# THS7002CPWP_Schematic_2.net
KiCad netlist of a schematic drawn in Altium Designer
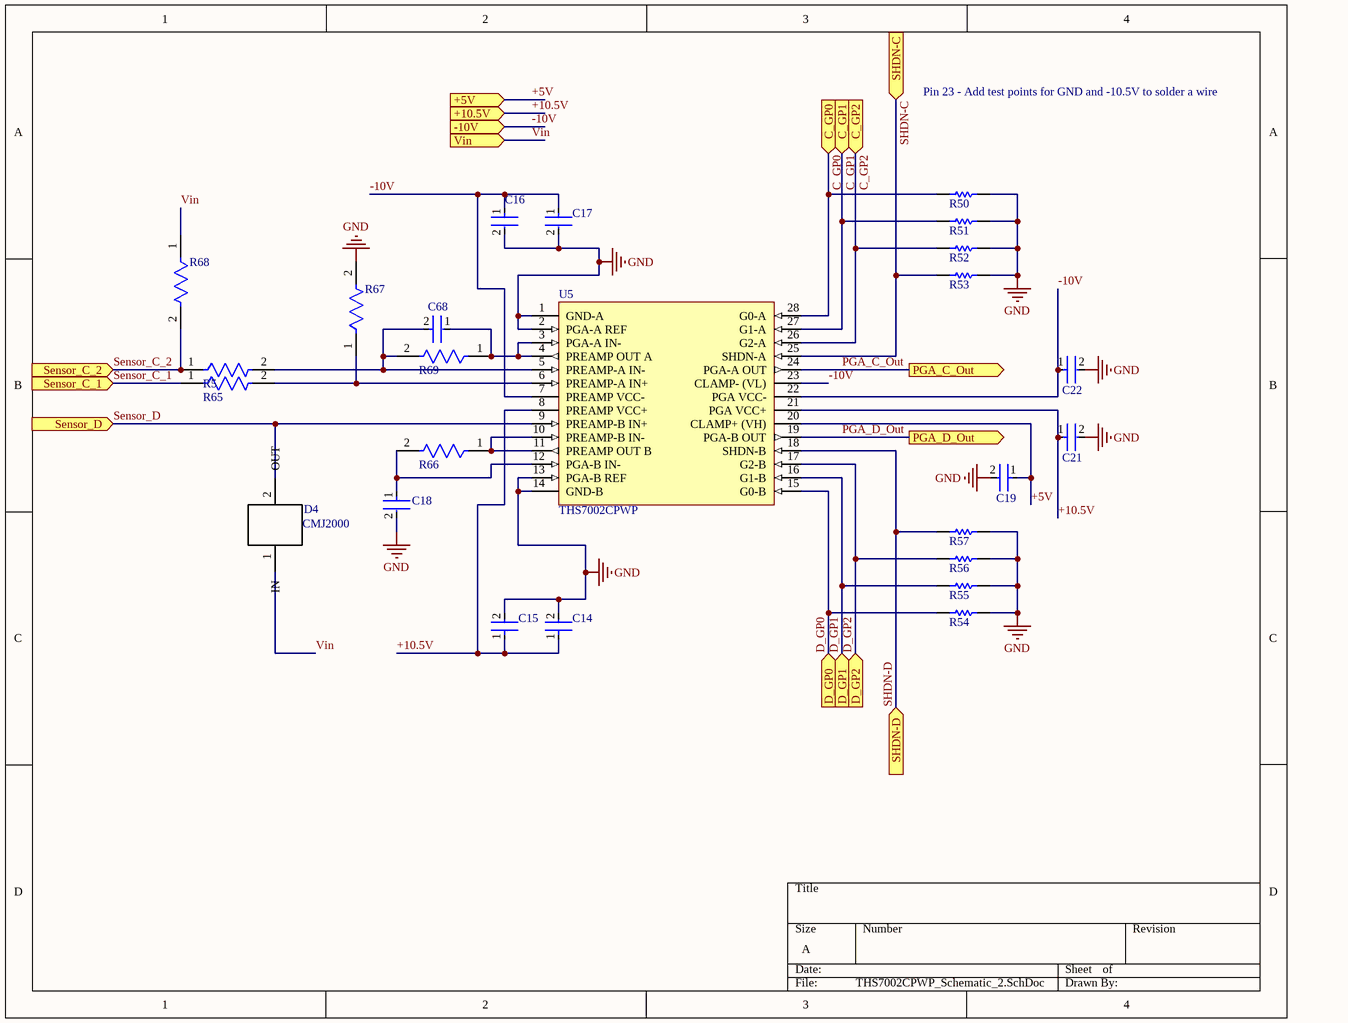
[diagram p0: THS7002CPWP_Schematic_2.SchDoc]

(export (version "E")
  (design (tool "Eeschema 10.0.6"))
  (components
    (comp (ref "C14")
      (value "~")
      (footprint "FP-C2012-060-0_2-IPC_A")
      (description "Multilayer Ceramic Capacitors 6.8μF ±10% 10V JB SMD 0805")
      (fields (field (name "TOLERANCE") "10%"))
      (libsource (lib "Capacitors") (part "b4654b650e69147ec39a6b967a45e02"))
    )
    (comp (ref "C15")
      (value "CC0603KRX7R7BB104")
      (footprint "FP-CC0603-DA-MFG")
      (description "CAP CER 0.1UF 16V X7R 0603")
      (fields
        (field (name "OCTOPART") "https://octopart.com/cc0603krx7r7bb104-yageo-192941")
        (field (name "TOLERANCE") "0.1")
      )
      (libsource (lib "Altium Content Vault") (part "11868f565c42a9108669ba33697ecf6"))
    )
    (comp (ref "C16")
      (value "CC0603KRX7R7BB104")
      (footprint "FP-CC0603-DA-MFG")
      (description "CAP CER 0.1UF 16V X7R 0603")
      (fields
        (field (name "OCTOPART") "https://octopart.com/cc0603krx7r7bb104-yageo-192941")
        (field (name "TOLERANCE") "0.1")
      )
      (libsource (lib "Altium Content Vault") (part "11868f565c42a9108669ba33697ecf6"))
    )
    (comp (ref "C17")
      (value "~")
      (footprint "FP-C2012-060-0_2-IPC_A")
      (description "Multilayer Ceramic Capacitors 6.8μF ±10% 10V JB SMD 0805")
      (fields (field (name "TOLERANCE") "10%"))
      (libsource (lib "Capacitors") (part "b4654b650e69147ec39a6b967a45e02"))
    )
    (comp (ref "C18")
      (value "GRM2195C1H622JA01D")
      (footprint "FP-GRM219-0_1-IPC_C")
      (description "Chip Multilayer Ceramic Capacitors for General Purpose, 0805, 6200pF, C0G, 30ppm/°C, 5%, 50V")
      (fields (field (name "TOLERANCE") "5%") (field (name "VOLTAGE") "50V"))
      (libsource (lib "Altium Content Vault") (part "02cd4be3c70576c341d710602a673aa"))
    )
    (comp (ref "C19")
      (value "~")
      (footprint "FP-C2012-060-0_2-IPC_A")
      (description "Multilayer Ceramic Capacitors 6.8μF ±10% 10V JB SMD 0805")
      (fields (field (name "TOLERANCE") "10%"))
      (libsource (lib "Capacitors") (part "b4654b650e69147ec39a6b967a45e02"))
    )
    (comp (ref "C21")
      (value "CC0603KRX7R7BB104")
      (footprint "FP-CC0603-DA-MFG")
      (description "CAP CER 0.1UF 16V X7R 0603")
      (fields
        (field (name "OCTOPART") "https://octopart.com/cc0603krx7r7bb104-yageo-192941")
        (field (name "TOLERANCE") "0.1")
      )
      (libsource (lib "Altium Content Vault") (part "11868f565c42a9108669ba33697ecf6"))
    )
    (comp (ref "C22")
      (value "CC0603KRX7R7BB104")
      (footprint "FP-CC0603-DA-MFG")
      (description "CAP CER 0.1UF 16V X7R 0603")
      (fields
        (field (name "OCTOPART") "https://octopart.com/cc0603krx7r7bb104-yageo-192941")
        (field (name "TOLERANCE") "0.1")
      )
      (libsource (lib "Altium Content Vault") (part "11868f565c42a9108669ba33697ecf6"))
    )
    (comp (ref "C68")
      (value "GRM31CR60J227ME11K")
      (footprint "FP-GRM31C-0_3-e0_3_0_9-IPC_C")
      (description "Chip Multilayer Ceramic Capacitors for General Purpose, 1206, 220uF, X5R, 15%, 20%, 6.3V")
      (fields (field (name "TOLERANCE") "20%"))
      (libsource (lib "Altium Content Vault") (part "f23184f103b6ebe33a8c269c53dcba6"))
    )
    (comp (ref "D4")
      (value "CMJ2000")
      (footprint "CMJ2000_Footprint")
      (description "DIODE CUR REG 100V 2.32MA 500MW")
      (libsource (lib "CMJ2000_Schematic") (part "CMJ2000"))
    )
    (comp (ref "R5")
      (value "CRCW0603499RFKEA")
      (footprint "FP-CRCW0603-e3-MFG")
      (description "RES Thick Film, 499Ω, 1%, 0.1W, 100ppm/°C, 0603")
      (fields (field (name "TOLERANCE") "1%"))
      (libsource (lib "Altium Content Vault") (part "1029c3af85768c4190bb7ad29bc67b5"))
    )
    (comp (ref "R50")
      (value "RC0603FR-073K3L")
      (footprint "RESC1608X55X25ML10T15")
      (description "Chip Resistor, 3.3 KOhm, +/- 1%, 0.1 W, -55 to 155 degC, 0603 (1608 Metric), RoHS, Tape and Reel")
      (fields (field (name "MANUFACTURER") "Yageo") (field (name "TOLERANCE") "1%"))
      (libsource (lib "Altium Content Vault") (part "RES-2"))
    )
    (comp (ref "R51")
      (value "RC0603FR-073K3L")
      (footprint "RESC1608X55X25ML10T15")
      (description "Chip Resistor, 3.3 KOhm, +/- 1%, 0.1 W, -55 to 155 degC, 0603 (1608 Metric), RoHS, Tape and Reel")
      (fields (field (name "MANUFACTURER") "Yageo") (field (name "TOLERANCE") "1%"))
      (libsource (lib "Altium Content Vault") (part "RES-2"))
    )
    (comp (ref "R52")
      (value "RC0603FR-073K3L")
      (footprint "RESC1608X55X25ML10T15")
      (description "Chip Resistor, 3.3 KOhm, +/- 1%, 0.1 W, -55 to 155 degC, 0603 (1608 Metric), RoHS, Tape and Reel")
      (fields (field (name "MANUFACTURER") "Yageo") (field (name "TOLERANCE") "1%"))
      (libsource (lib "Altium Content Vault") (part "RES-2"))
    )
    (comp (ref "R53")
      (value "RC0603FR-073K3L")
      (footprint "RESC1608X55X25ML10T15")
      (description "Chip Resistor, 3.3 KOhm, +/- 1%, 0.1 W, -55 to 155 degC, 0603 (1608 Metric), RoHS, Tape and Reel")
      (fields (field (name "MANUFACTURER") "Yageo") (field (name "TOLERANCE") "1%"))
      (libsource (lib "Altium Content Vault") (part "RES-2"))
    )
    (comp (ref "R54")
      (value "RC0603FR-073K3L")
      (footprint "RESC1608X55X25ML10T15")
      (description "Chip Resistor, 3.3 KOhm, +/- 1%, 0.1 W, -55 to 155 degC, 0603 (1608 Metric), RoHS, Tape and Reel")
      (fields (field (name "MANUFACTURER") "Yageo") (field (name "TOLERANCE") "1%"))
      (libsource (lib "Altium Content Vault") (part "RES-2"))
    )
    (comp (ref "R55")
      (value "RC0603FR-073K3L")
      (footprint "RESC1608X55X25ML10T15")
      (description "Chip Resistor, 3.3 KOhm, +/- 1%, 0.1 W, -55 to 155 degC, 0603 (1608 Metric), RoHS, Tape and Reel")
      (fields (field (name "MANUFACTURER") "Yageo") (field (name "TOLERANCE") "1%"))
      (libsource (lib "Altium Content Vault") (part "RES-2"))
    )
    (comp (ref "R56")
      (value "RC0603FR-073K3L")
      (footprint "RESC1608X55X25ML10T15")
      (description "Chip Resistor, 3.3 KOhm, +/- 1%, 0.1 W, -55 to 155 degC, 0603 (1608 Metric), RoHS, Tape and Reel")
      (fields (field (name "MANUFACTURER") "Yageo") (field (name "TOLERANCE") "1%"))
      (libsource (lib "Altium Content Vault") (part "RES-2"))
    )
    (comp (ref "R57")
      (value "RC0603FR-073K3L")
      (footprint "RESC1608X55X25ML10T15")
      (description "Chip Resistor, 3.3 KOhm, +/- 1%, 0.1 W, -55 to 155 degC, 0603 (1608 Metric), RoHS, Tape and Reel")
      (fields (field (name "MANUFACTURER") "Yageo") (field (name "TOLERANCE") "1%"))
      (libsource (lib "Altium Content Vault") (part "RES-2"))
    )
    (comp (ref "R65")
      (value "CRCW0603499RFKEA")
      (footprint "FP-CRCW0603-e3-MFG")
      (description "RES Thick Film, 499Ω, 1%, 0.1W, 100ppm/°C, 0603")
      (fields (field (name "TOLERANCE") "1%"))
      (libsource (lib "Altium Content Vault") (part "1029c3af85768c4190bb7ad29bc67b5"))
    )
    (comp (ref "R66")
      (value "CRCW0603499RFKEA")
      (footprint "FP-CRCW0603-e3-MFG")
      (description "RES Thick Film, 499Ω, 1%, 0.1W, 100ppm/°C, 0603")
      (fields (field (name "TOLERANCE") "1%"))
      (libsource (lib "Altium Content Vault") (part "1029c3af85768c4190bb7ad29bc67b5"))
    )
    (comp (ref "R67")
      (value "CRCW0603499RFKEA")
      (footprint "FP-CRCW0603-e3-MFG")
      (description "RES Thick Film, 499Ω, 1%, 0.1W, 100ppm/°C, 0603")
      (fields (field (name "TOLERANCE") "1%"))
      (libsource (lib "Altium Content Vault") (part "1029c3af85768c4190bb7ad29bc67b5"))
    )
    (comp (ref "R68")
      (value "RC0603FR-07100KL")
      (footprint "FP-RC0603-0_55-MFG")
      (description "RES SMD 100K OHM 1% 1/10W 0603")
      (fields (field (name "TOLERANCE") "1%"))
      (libsource (lib "Altium Content Vault") (part "1029c3af85768c4190bb7ad29bc67b5"))
    )
    (comp (ref "R69")
      (value "CRCW0603499RFKEA")
      (footprint "FP-CRCW0603-e3-MFG")
      (description "RES Thick Film, 499Ω, 1%, 0.1W, 100ppm/°C, 0603")
      (fields (field (name "TOLERANCE") "1%"))
      (libsource (lib "Altium Content Vault") (part "1029c3af85768c4190bb7ad29bc67b5"))
    )
    (comp (ref "U5")
      (value "THS7002CPWP")
      (footprint "THS7002CPWP")
      (fields (field (name "MANUFACTURER") "Texas Instruments"))
      (libsource (lib "THS7002CPWP_Symbol") (part "CMP-0988-00132-2"))
    )
  )
  (nets
    (net (code "1") (name "/+5V") (class "Default")
      (node (ref "C19") (pin "1") (pinfunction "1_1") (pintype "passive"))
      (node (ref "U5") (pin "20") (pinfunction "CLAMP+_(VH)_20") (pintype "power_in"))
    )
    (net (code "2") (name "/+10.5V") (class "Default")
      (node (ref "C14") (pin "1") (pinfunction "1_1") (pintype "passive"))
      (node (ref "C15") (pin "1") (pinfunction "1_1") (pintype "passive"))
      (node (ref "C21") (pin "1") (pinfunction "1_1") (pintype "passive"))
      (node (ref "U5") (pin "21") (pinfunction "PGA_VCC+_21") (pintype "power_in"))
      (node (ref "U5") (pin "8") (pinfunction "PREAMP_VCC+_8") (pintype "power_in"))
    )
    (net (code "3") (name "/-10V") (class "Default")
      (node (ref "C16") (pin "1") (pinfunction "1_1") (pintype "passive"))
      (node (ref "C17") (pin "1") (pinfunction "1_1") (pintype "passive"))
      (node (ref "C22") (pin "1") (pinfunction "1_1") (pintype "passive"))
      (node (ref "U5") (pin "22") (pinfunction "PGA_VCC-_22") (pintype "power_in"))
      (node (ref "U5") (pin "23") (pinfunction "CLAMP-_(VL)_23") (pintype "power_in"))
      (node (ref "U5") (pin "7") (pinfunction "PREAMP_VCC-_7") (pintype "power_in"))
    )
    (net (code "4") (name "/C_GP0") (class "Default")
      (node (ref "R50") (pin "2") (pinfunction "2_2") (pintype "passive"))
      (node (ref "U5") (pin "28") (pinfunction "G0-A_28") (pintype "input"))
    )
    (net (code "5") (name "/C_GP1") (class "Default")
      (node (ref "R51") (pin "2") (pinfunction "2_2") (pintype "passive"))
      (node (ref "U5") (pin "27") (pinfunction "G1-A_27") (pintype "input"))
    )
    (net (code "6") (name "/C_GP2") (class "Default")
      (node (ref "R52") (pin "2") (pinfunction "2_2") (pintype "passive"))
      (node (ref "U5") (pin "26") (pinfunction "G2-A_26") (pintype "input"))
    )
    (net (code "7") (name "/D_GP0") (class "Default")
      (node (ref "R54") (pin "2") (pinfunction "2_2") (pintype "passive"))
      (node (ref "U5") (pin "15") (pinfunction "G0-B_15") (pintype "input"))
    )
    (net (code "8") (name "/D_GP1") (class "Default")
      (node (ref "R55") (pin "2") (pinfunction "2_2") (pintype "passive"))
      (node (ref "U5") (pin "16") (pinfunction "G1-B_16") (pintype "input"))
    )
    (net (code "9") (name "/D_GP2") (class "Default")
      (node (ref "R56") (pin "2") (pinfunction "2_2") (pintype "passive"))
      (node (ref "U5") (pin "17") (pinfunction "G2-B_17") (pintype "input"))
    )
    (net (code "10") (name "/PGA_C_Out") (class "Default")
      (node (ref "U5") (pin "24") (pinfunction "PGA-A_OUT_24") (pintype "output"))
    )
    (net (code "11") (name "/PGA_D_Out") (class "Default")
      (node (ref "U5") (pin "19") (pinfunction "PGA-B_OUT_19") (pintype "output"))
    )
    (net (code "12") (name "/SHDN-C") (class "Default")
      (node (ref "R53") (pin "2") (pinfunction "2_2") (pintype "passive"))
      (node (ref "U5") (pin "25") (pinfunction "SHDN-A_25") (pintype "input"))
    )
    (net (code "13") (name "/SHDN-D") (class "Default")
      (node (ref "R57") (pin "2") (pinfunction "2_2") (pintype "passive"))
      (node (ref "U5") (pin "18") (pinfunction "SHDN-B_18") (pintype "input"))
    )
    (net (code "14") (name "/Sensor_C_1") (class "Default")
      (node (ref "R65") (pin "1") (pinfunction "1_1") (pintype "passive"))
    )
    (net (code "15") (name "/Sensor_C_2") (class "Default")
      (node (ref "R5") (pin "1") (pinfunction "1_1") (pintype "passive"))
      (node (ref "R68") (pin "2") (pinfunction "2_2") (pintype "passive"))
    )
    (net (code "16") (name "/Sensor_D") (class "Default")
      (node (ref "U5") (pin "9") (pinfunction "PREAMP-B_IN+_9") (pintype "input"))
    )
    (net (code "17") (name "/Vin") (class "Default")
      (node (ref "R68") (pin "1") (pinfunction "1_1") (pintype "passive"))
    )
    (net (code "18") (name "GND") (class "Default")
      (node (ref "C14") (pin "2") (pinfunction "2_2") (pintype "passive"))
      (node (ref "C15") (pin "2") (pinfunction "2_2") (pintype "passive"))
      (node (ref "C16") (pin "2") (pinfunction "2_2") (pintype "passive"))
      (node (ref "C17") (pin "2") (pinfunction "2_2") (pintype "passive"))
      (node (ref "C18") (pin "2") (pinfunction "2_2") (pintype "passive"))
      (node (ref "C19") (pin "2") (pinfunction "2_2") (pintype "passive"))
      (node (ref "C21") (pin "2") (pinfunction "2_2") (pintype "passive"))
      (node (ref "C22") (pin "2") (pinfunction "2_2") (pintype "passive"))
      (node (ref "R50") (pin "1") (pinfunction "1_1") (pintype "passive"))
      (node (ref "R51") (pin "1") (pinfunction "1_1") (pintype "passive"))
      (node (ref "R52") (pin "1") (pinfunction "1_1") (pintype "passive"))
      (node (ref "R53") (pin "1") (pinfunction "1_1") (pintype "passive"))
      (node (ref "R54") (pin "1") (pinfunction "1_1") (pintype "passive"))
      (node (ref "R55") (pin "1") (pinfunction "1_1") (pintype "passive"))
      (node (ref "R56") (pin "1") (pinfunction "1_1") (pintype "passive"))
      (node (ref "R57") (pin "1") (pinfunction "1_1") (pintype "passive"))
      (node (ref "R67") (pin "2") (pinfunction "2_2") (pintype "passive"))
      (node (ref "U5") (pin "1") (pinfunction "GND-A_1") (pintype "power_in"))
      (node (ref "U5") (pin "13") (pinfunction "PGA-B_REF_13") (pintype "input"))
      (node (ref "U5") (pin "14") (pinfunction "GND-B_14") (pintype "power_in"))
      (node (ref "U5") (pin "2") (pinfunction "PGA-A_REF_2") (pintype "input"))
    )
    (net (code "19") (name "Net-(U5-PGA-A_IN-)") (class "Default")
      (node (ref "C68") (pin "1") (pinfunction "1_1") (pintype "passive"))
      (node (ref "R69") (pin "1") (pinfunction "1_1") (pintype "passive"))
      (node (ref "U5") (pin "3") (pinfunction "PGA-A_IN-_3") (pintype "input"))
      (node (ref "U5") (pin "4") (pinfunction "PREAMP_OUT_A_4") (pintype "output"))
    )
    (net (code "20") (name "Net-(U5-PGA-B_IN-)") (class "Default")
      (node (ref "C18") (pin "1") (pinfunction "1_1") (pintype "passive"))
      (node (ref "R66") (pin "2") (pinfunction "2_2") (pintype "passive"))
      (node (ref "U5") (pin "12") (pinfunction "PGA-B_IN-_12") (pintype "input"))
    )
    (net (code "21") (name "Net-(U5-PREAMP-A_IN+)") (class "Default")
      (node (ref "R65") (pin "2") (pinfunction "2_2") (pintype "passive"))
      (node (ref "R67") (pin "1") (pinfunction "1_1") (pintype "passive"))
      (node (ref "U5") (pin "6") (pinfunction "PREAMP-A_IN+_6") (pintype "input"))
    )
    (net (code "22") (name "Net-(U5-PREAMP-A_IN-)") (class "Default")
      (node (ref "C68") (pin "2") (pinfunction "2_2") (pintype "passive"))
      (node (ref "R5") (pin "2") (pinfunction "2_2") (pintype "passive"))
      (node (ref "R69") (pin "2") (pinfunction "2_2") (pintype "passive"))
      (node (ref "U5") (pin "5") (pinfunction "PREAMP-A_IN-_5") (pintype "input"))
    )
    (net (code "23") (name "Net-(U5-PREAMP-B_IN-)") (class "Default")
      (node (ref "R66") (pin "1") (pinfunction "1_1") (pintype "passive"))
      (node (ref "U5") (pin "10") (pinfunction "PREAMP-B_IN-_10") (pintype "input"))
      (node (ref "U5") (pin "11") (pinfunction "PREAMP_OUT_B_11") (pintype "output"))
    )
    (net (code "24") (name "unconnected-(D4-IN-Pad1)") (class "Default")
      (node (ref "D4") (pin "1") (pinfunction "IN_1") (pintype "passive"))
    )
    (net (code "25") (name "unconnected-(D4-OUT-Pad2)") (class "Default")
      (node (ref "D4") (pin "2") (pinfunction "OUT_2") (pintype "passive"))
    )
  )
)
